# PCB_Project_11_3.net
KiCad netlist of a schematic drawn in Altium Designer
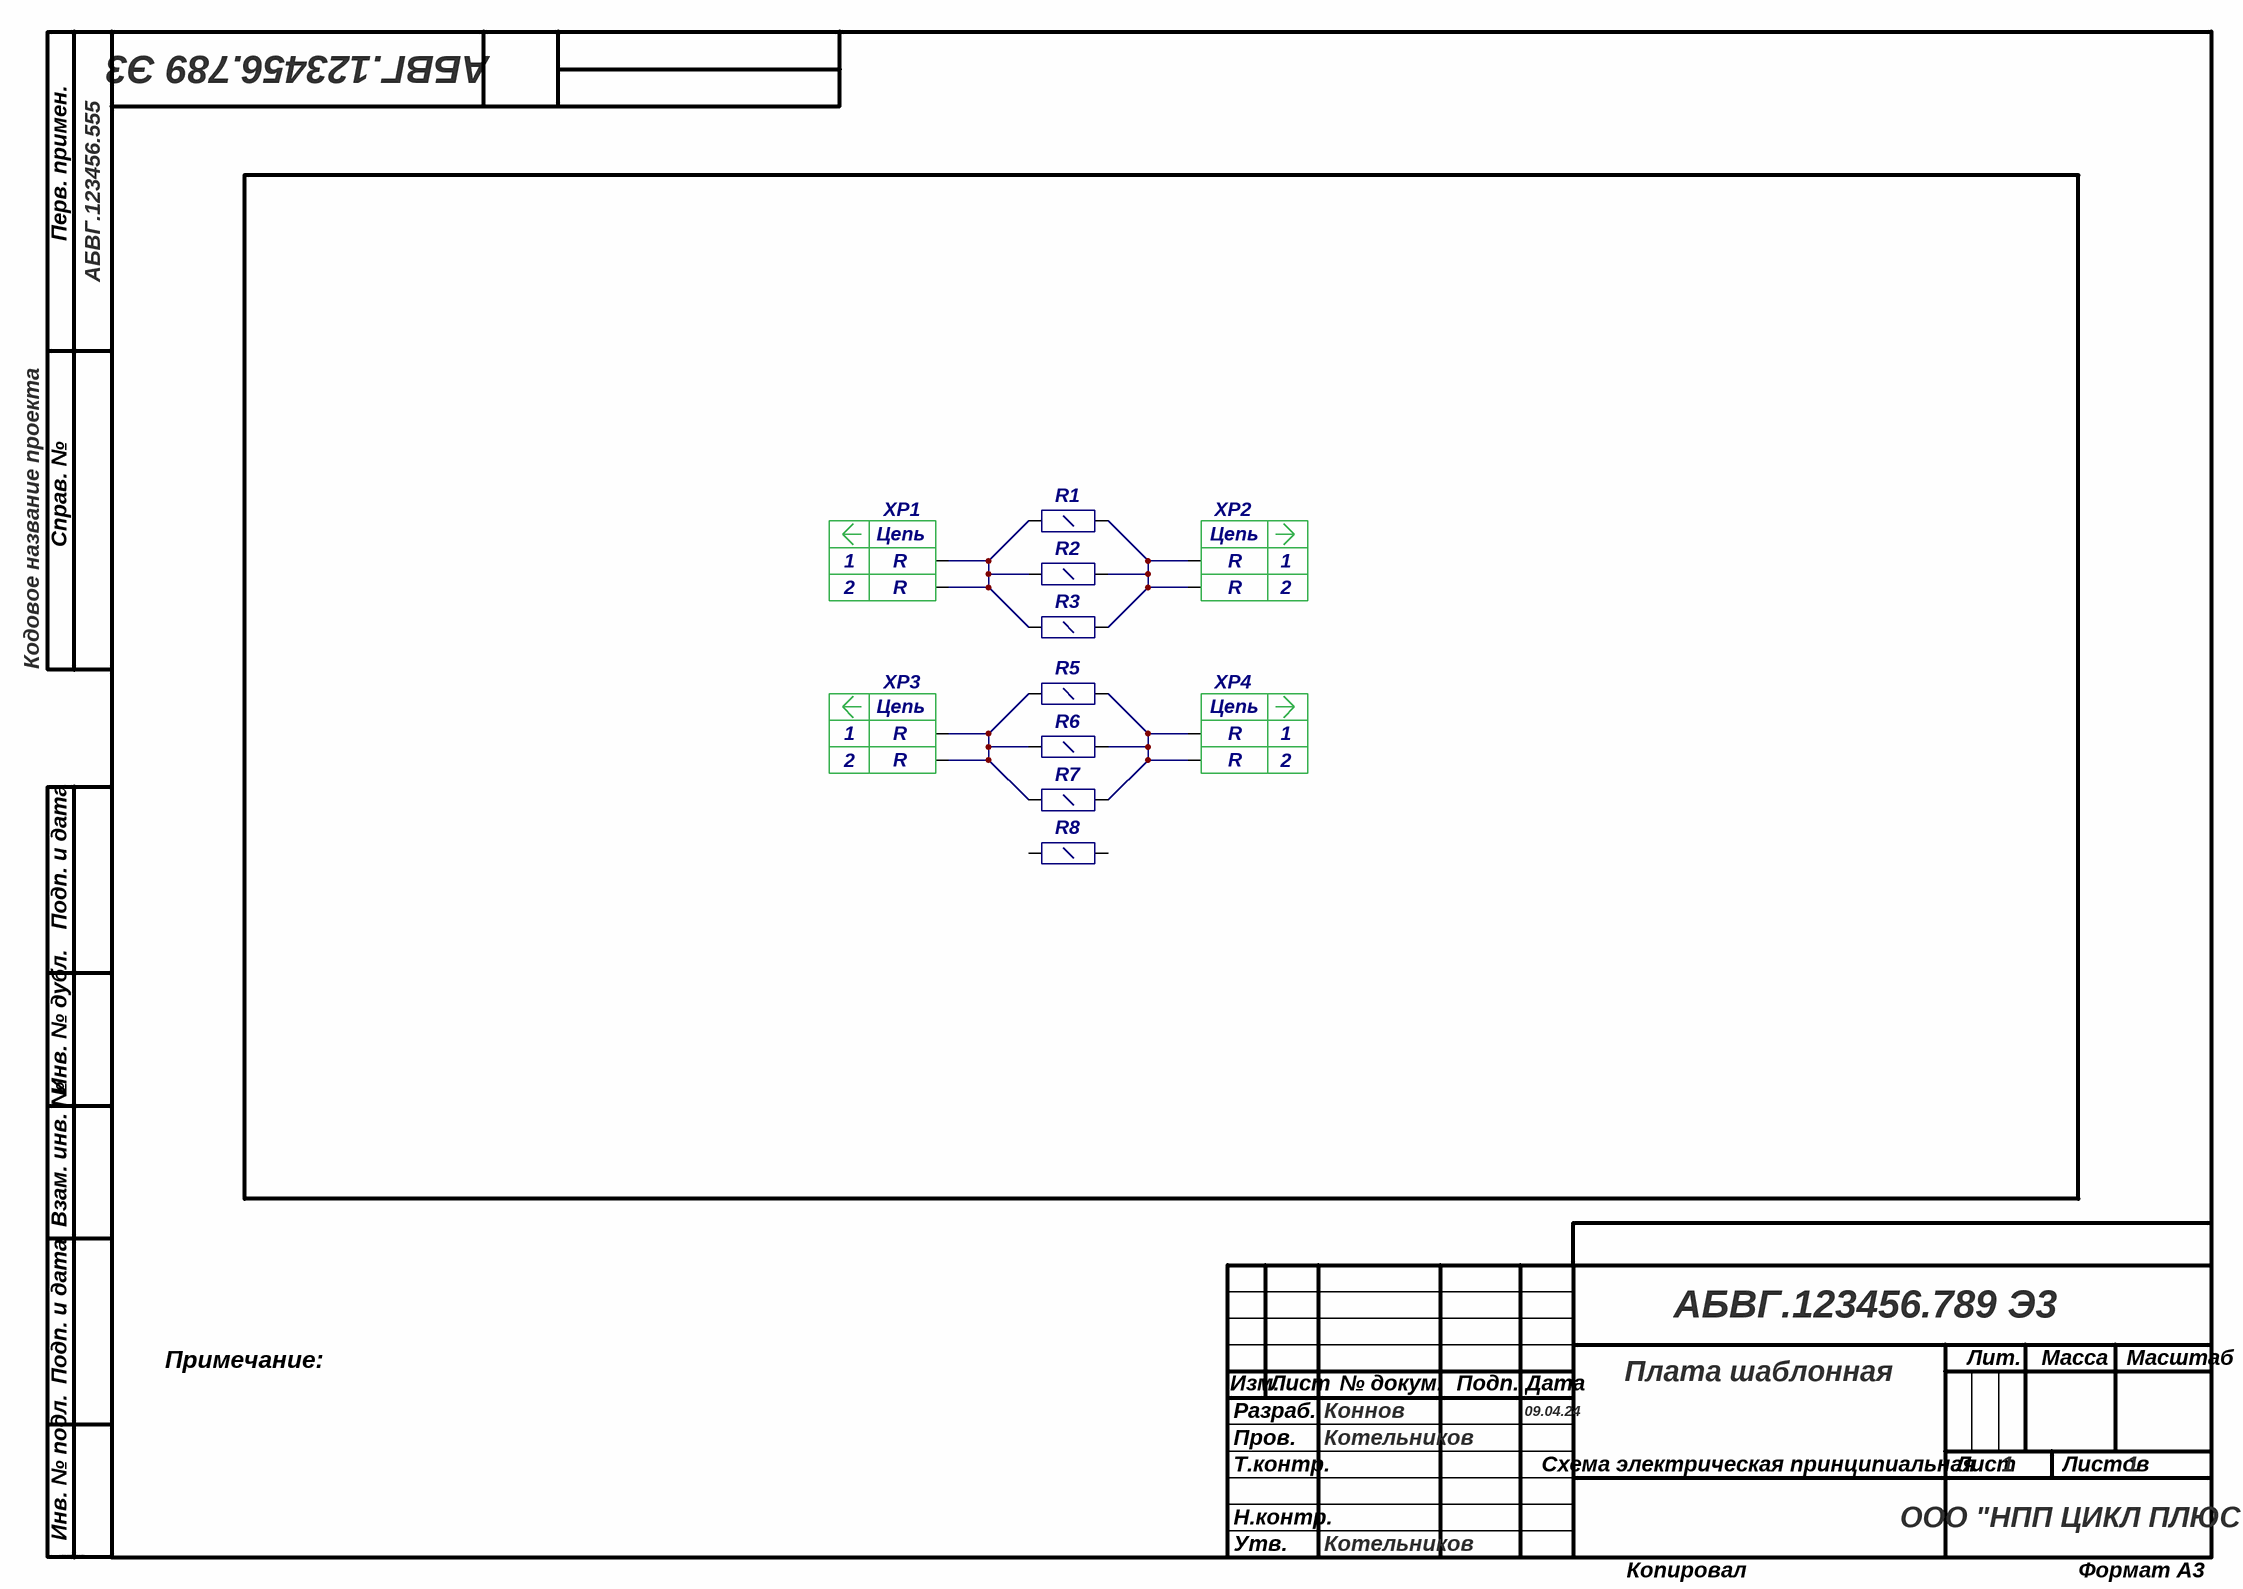
[diagram p0: PCB_Project_11 Э3 (Питание).SchDoc]

(export (version "E")
  (design (tool "Eeschema 10.0.6"))
  (components
    (comp (ref "R1")
      (value "RC1206FR-072RL")
      (footprint "Resistors_SMD:1206_(RES)")
      (description "RES SMD 2 OHM 1% 1/4W 1206")
      (fields (field (name "MANUFACTURER") "Yageo") (field (name "TOLERANCE") "1%"))
      (libsource (lib "Resistors_SMD_Yageo") (part "RC1206FR-072RL"))
    )
    (comp (ref "R2")
      (value "RC1206FR-072RL")
      (footprint "Resistors_SMD:1206_(RES)")
      (description "RES SMD 2 OHM 1% 1/4W 1206")
      (fields (field (name "MANUFACTURER") "Yageo") (field (name "TOLERANCE") "1%"))
      (libsource (lib "Resistors_SMD_Yageo") (part "RC1206FR-072RL"))
    )
    (comp (ref "R3")
      (value "RC1206FR-072RL")
      (footprint "Resistors_SMD:1206_(RES)")
      (description "RES SMD 2 OHM 1% 1/4W 1206")
      (fields (field (name "MANUFACTURER") "Yageo") (field (name "TOLERANCE") "1%"))
      (libsource (lib "Resistors_SMD_Yageo") (part "RC1206FR-072RL"))
    )
    (comp (ref "R5")
      (value "RC1206FR-072RL")
      (footprint "Resistors_SMD:1206_(RES)")
      (description "RES SMD 2 OHM 1% 1/4W 1206")
      (fields (field (name "MANUFACTURER") "Yageo") (field (name "TOLERANCE") "1%"))
      (libsource (lib "Resistors_SMD_Yageo") (part "RC1206FR-072RL"))
    )
    (comp (ref "R6")
      (value "RC1206FR-072RL")
      (footprint "Resistors_SMD:1206_(RES)")
      (description "RES SMD 2 OHM 1% 1/4W 1206")
      (fields (field (name "MANUFACTURER") "Yageo") (field (name "TOLERANCE") "1%"))
      (libsource (lib "Resistors_SMD_Yageo") (part "RC1206FR-072RL"))
    )
    (comp (ref "R7")
      (value "RC1206FR-072RL")
      (footprint "Resistors_SMD:1206_(RES)")
      (description "RES SMD 2 OHM 1% 1/4W 1206")
      (fields (field (name "MANUFACTURER") "Yageo") (field (name "TOLERANCE") "1%"))
      (libsource (lib "Resistors_SMD_Yageo") (part "RC1206FR-072RL"))
    )
    (comp (ref "R8")
      (value "RC1206FR-072RL")
      (footprint "Resistors_SMD:1206_(RES)")
      (description "RES SMD 2 OHM 1% 1/4W 1206")
      (fields (field (name "MANUFACTURER") "Yageo") (field (name "TOLERANCE") "1%"))
      (libsource (lib "Resistors_SMD_Yageo") (part "RC1206FR-072RL"))
    )
    (comp (ref "XP1")
      (value "15EDGVM-3.5-02P")
      (footprint "Connectors_DEGSON:15EDGVM-3.5-02P-14-00A(H)")
      (description "vertical, screw, 7A, 250V, 3.5mm")
      (fields (field (name "MANUFACTURER") "DEGSON") (field (name "2") "R") (field (name "1") "R"))
      (libsource (lib "Connectors_DEGSON") (part "15EDGVM-3.5-02P"))
    )
    (comp (ref "XP2")
      (value "15EDGVM-3.5-02P")
      (footprint "Connectors_DEGSON:15EDGVM-3.5-02P-14-00A(H)")
      (description "vertical, screw, 7A, 250V, 3.5mm")
      (fields (field (name "MANUFACTURER") "DEGSON") (field (name "2") "R") (field (name "1") "R"))
      (libsource (lib "Connectors_DEGSON") (part "15EDGVM-3.5-02P"))
    )
    (comp (ref "XP3")
      (value "15EDGVM-3.5-02P")
      (footprint "Connectors_DEGSON:15EDGVM-3.5-02P-14-00A(H)")
      (description "vertical, screw, 7A, 250V, 3.5mm")
      (fields (field (name "MANUFACTURER") "DEGSON") (field (name "2") "R") (field (name "1") "R"))
      (libsource (lib "Connectors_DEGSON") (part "15EDGVM-3.5-02P"))
    )
    (comp (ref "XP4")
      (value "15EDGVM-3.5-02P")
      (footprint "Connectors_DEGSON:15EDGVM-3.5-02P-14-00A(H)")
      (description "vertical, screw, 7A, 250V, 3.5mm")
      (fields (field (name "MANUFACTURER") "DEGSON") (field (name "2") "R") (field (name "1") "R"))
      (libsource (lib "Connectors_DEGSON") (part "15EDGVM-3.5-02P"))
    )
  )
  (nets
    (net (code "1") (name "Net-(R1-Pad1)") (class "Default")
      (node (ref "R1") (pin "1") (pinfunction "1_1") (pintype "passive"))
      (node (ref "R2") (pin "1") (pinfunction "1_1") (pintype "passive"))
      (node (ref "R3") (pin "1") (pinfunction "1_1") (pintype "passive"))
      (node (ref "XP1") (pin "1") (pinfunction "1_1") (pintype "passive"))
      (node (ref "XP1") (pin "2") (pinfunction "2_2") (pintype "passive"))
    )
    (net (code "2") (name "Net-(R1-Pad2)") (class "Default")
      (node (ref "R1") (pin "2") (pinfunction "2_2") (pintype "passive"))
      (node (ref "R2") (pin "2") (pinfunction "2_2") (pintype "passive"))
      (node (ref "R3") (pin "2") (pinfunction "2_2") (pintype "passive"))
      (node (ref "XP2") (pin "1") (pinfunction "1_1") (pintype "passive"))
      (node (ref "XP2") (pin "2") (pinfunction "2_2") (pintype "passive"))
    )
    (net (code "3") (name "Net-(R5-Pad1)") (class "Default")
      (node (ref "R5") (pin "1") (pinfunction "1_1") (pintype "passive"))
      (node (ref "R6") (pin "1") (pinfunction "1_1") (pintype "passive"))
      (node (ref "R7") (pin "1") (pinfunction "1_1") (pintype "passive"))
      (node (ref "XP3") (pin "1") (pinfunction "1_1") (pintype "passive"))
      (node (ref "XP3") (pin "2") (pinfunction "2_2") (pintype "passive"))
    )
    (net (code "4") (name "Net-(R5-Pad2)") (class "Default")
      (node (ref "R5") (pin "2") (pinfunction "2_2") (pintype "passive"))
      (node (ref "R6") (pin "2") (pinfunction "2_2") (pintype "passive"))
      (node (ref "R7") (pin "2") (pinfunction "2_2") (pintype "passive"))
      (node (ref "XP4") (pin "1") (pinfunction "1_1") (pintype "passive"))
      (node (ref "XP4") (pin "2") (pinfunction "2_2") (pintype "passive"))
    )
    (net (code "5") (name "unconnected-(R8-Pad1)") (class "Default")
      (node (ref "R8") (pin "1") (pinfunction "1_1") (pintype "passive"))
    )
    (net (code "6") (name "unconnected-(R8-Pad2)") (class "Default")
      (node (ref "R8") (pin "2") (pinfunction "2_2") (pintype "passive"))
    )
  )
)
